# 24vAudioSupply.net
KiCad netlist of a schematic drawn in EAGLE
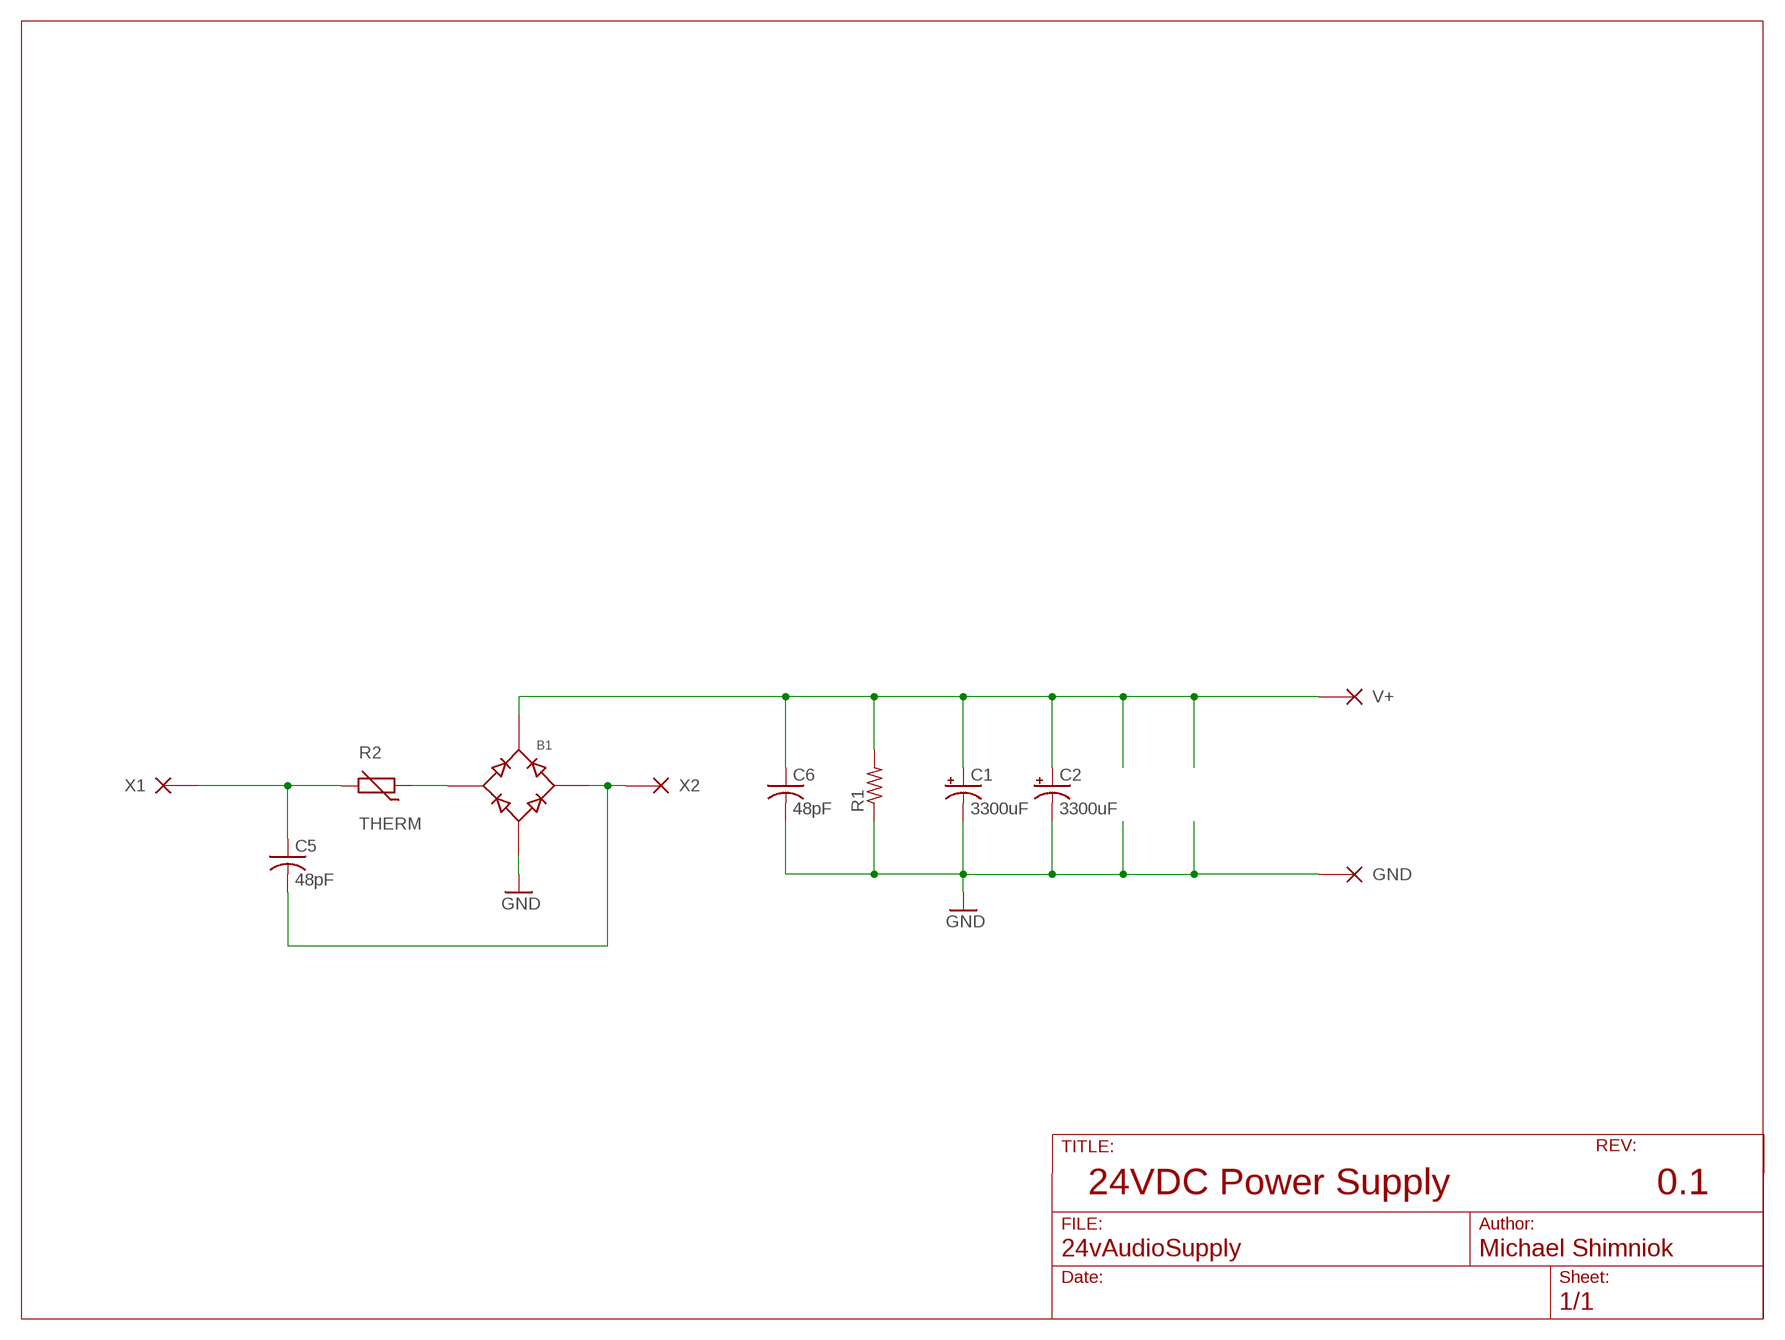
[diagram p0: schematic, sheet 1]

(export (version "E")
  (design (tool "Eeschema 10.0.6"))
  (components
    (comp (ref "B1")
      (value "RECTIFIER-GBPC-W")
      (footprint "eagle-import:GBPC-W")
      (libsource (lib "eagle-import") (part "RECTIFIER-GBPC-W"))
    )
    (comp (ref "C1")
      (value "3300uF")
      (footprint "eagle-import:E7,5-18")
      (libsource (lib "eagle-import") (part "CPOL-USE7.5-18"))
    )
    (comp (ref "C2")
      (value "3300uF")
      (footprint "eagle-import:E7,5-18")
      (libsource (lib "eagle-import") (part "CPOL-USE7.5-18"))
    )
    (comp (ref "C5")
      (value "48pF")
      (footprint "eagle-import:C075")
      (libsource (lib "eagle-import") (part "C-075PTH"))
    )
    (comp (ref "C6")
      (value "48pF")
      (footprint "eagle-import:C075")
      (libsource (lib "eagle-import") (part "C-075PTH"))
    )
    (comp (ref "R1")
      (value "R0204/7-PTH")
      (footprint "eagle-import:0204_7")
      (libsource (lib "eagle-import") (part "R0204/7-PTH"))
    )
    (comp (ref "R2")
      (value "THERM")
      (footprint "eagle-import:R-7,5")
      (libsource (lib "eagle-import") (part "THERMISTOR-7,5"))
    )
    (comp (ref "X1")
      (value "X1")
      (footprint "eagle-import:PAD_14GA")
      (libsource (lib "eagle-import") (part "WIREPAD_14GA"))
    )
    (comp (ref "X2")
      (value "X2")
      (footprint "eagle-import:PAD_14GA")
      (libsource (lib "eagle-import") (part "WIREPAD_14GA"))
    )
    (comp (ref "X3")
      (value "V+")
      (footprint "eagle-import:PAD_12GA")
      (libsource (lib "eagle-import") (part "WIREPAD_12GA"))
    )
    (comp (ref "X4")
      (value "GND")
      (footprint "eagle-import:PAD_12GA")
      (libsource (lib "eagle-import") (part "WIREPAD_12GA"))
    )
  )
  (nets
    (net (code "1") (name "GND") (class "Default")
      (node (ref "B1") (pin "V-") (pinfunction "-_V-") (pintype "bidirectional"))
      (node (ref "C1") (pin "-") (pinfunction "-_-") (pintype "passive"))
      (node (ref "C2") (pin "-") (pinfunction "-_-") (pintype "passive"))
      (node (ref "C6") (pin "2") (pinfunction "-_2") (pintype "passive"))
      (node (ref "R1") (pin "1") (pinfunction "1_1") (pintype "passive"))
      (node (ref "X4") (pin "P$1") (pinfunction "P_P$1") (pintype "bidirectional"))
    )
    (net (code "2") (name "Net-(B1-+)") (class "Default")
      (node (ref "B1") (pin "V+") (pinfunction "+_V+") (pintype "bidirectional"))
      (node (ref "C1") (pin "+") (pinfunction "+_+") (pintype "passive"))
      (node (ref "C2") (pin "+") (pinfunction "+_+") (pintype "passive"))
      (node (ref "C6") (pin "1") (pinfunction "+_1") (pintype "passive"))
      (node (ref "R1") (pin "2") (pinfunction "2_2") (pintype "passive"))
      (node (ref "X3") (pin "P$1") (pinfunction "P_P$1") (pintype "bidirectional"))
    )
    (net (code "3") (name "Net-(B1-PadAC1)") (class "Default")
      (node (ref "B1") (pin "AC1") (pinfunction "AC1_AC1") (pintype "bidirectional"))
      (node (ref "R2") (pin "1") (pinfunction "1_1") (pintype "passive"))
    )
    (net (code "4") (name "Net-(C5-+)") (class "Default")
      (node (ref "C5") (pin "1") (pinfunction "+_1") (pintype "passive"))
      (node (ref "R2") (pin "2") (pinfunction "2_2") (pintype "passive"))
      (node (ref "X1") (pin "P$1") (pinfunction "P_P$1") (pintype "bidirectional"))
    )
    (net (code "5") (name "Net-(C5--)") (class "Default")
      (node (ref "B1") (pin "AC2") (pinfunction "AC2_AC2") (pintype "bidirectional"))
      (node (ref "C5") (pin "2") (pinfunction "-_2") (pintype "passive"))
      (node (ref "X2") (pin "P$1") (pinfunction "P_P$1") (pintype "bidirectional"))
    )
  )
)
